# User.net
KiCad netlist of a schematic drawn in Altium Designer
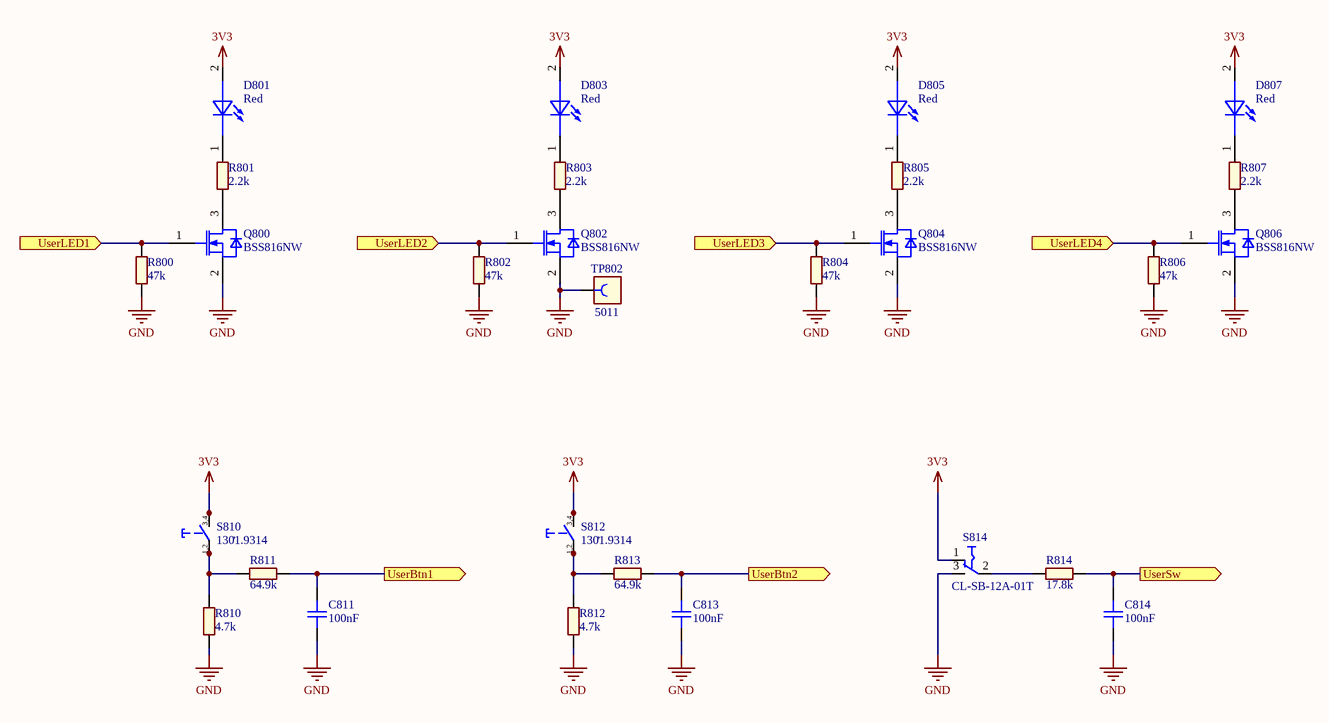
[diagram p0: User.SchDoc]

(export (version "E")
  (design (tool "Eeschema 10.0.6"))
  (components
    (comp (ref "C811")
      (value "100nF")
      (footprint "CAPC1608X90N-2")
      (description "CAP / CERA / 100nF / 50V / 10% / X7R (EIA) / -55°C to 125°C / 0603 / SMD / -")
      (fields (field (name "MANUFACTURER") "AVX"))
      (libsource (lib "PCBLibraryData") (part "CAP-SGL-STD-02P_00000001"))
    )
    (comp (ref "C813")
      (value "100nF")
      (footprint "CAPC1608X90N-2")
      (description "CAP / CERA / 100nF / 50V / 10% / X7R (EIA) / -55°C to 125°C / 0603 / SMD / -")
      (fields (field (name "MANUFACTURER") "AVX"))
      (libsource (lib "PCBLibraryData") (part "CAP-SGL-STD-02P_00000001"))
    )
    (comp (ref "C814")
      (value "100nF")
      (footprint "CAPC1608X90N-2")
      (description "CAP / CERA / 100nF / 50V / 10% / X7R (EIA) / -55°C to 125°C / 0603 / SMD / -")
      (fields (field (name "MANUFACTURER") "AVX"))
      (libsource (lib "PCBLibraryData") (part "CAP-SGL-STD-02P_00000001"))
    )
    (comp (ref "D801")
      (value "Red")
      (footprint "LEDSC160X80X80-2N-1")
      (description "WL-SMCW SMT Mono-color Chip LED Waterclear, Red,630nm")
      (fields (field (name "MANUFACTURER") "Wurth Elektronik"))
      (libsource (lib "PCBLibraryData") (part "d_led_a"))
    )
    (comp (ref "D803")
      (value "Red")
      (footprint "LEDSC160X80X80-2N-1")
      (description "WL-SMCW SMT Mono-color Chip LED Waterclear, Red,630nm")
      (fields (field (name "MANUFACTURER") "Wurth Elektronik"))
      (libsource (lib "PCBLibraryData") (part "d_led_a"))
    )
    (comp (ref "D805")
      (value "Red")
      (footprint "LEDSC160X80X80-2N-1")
      (description "WL-SMCW SMT Mono-color Chip LED Waterclear, Red,630nm")
      (fields (field (name "MANUFACTURER") "Wurth Elektronik"))
      (libsource (lib "PCBLibraryData") (part "d_led_a"))
    )
    (comp (ref "D807")
      (value "Red")
      (footprint "LEDSC160X80X80-2N-1")
      (description "WL-SMCW SMT Mono-color Chip LED Waterclear, Red,630nm")
      (fields (field (name "MANUFACTURER") "Wurth Elektronik"))
      (libsource (lib "PCBLibraryData") (part "d_led_a"))
    )
    (comp (ref "Q800")
      (value "BSS816NW")
      (footprint "SOT65P210X100-3N-1-V")
      (description "OptiMOS 2 Small-Signal-Transistor")
      (fields (field (name "MANUFACTURER") "Infineon Technologies"))
      (libsource (lib "PCBLibraryData") (part "igfet_n_ch_dep_dio_1g2s3d_3p"))
    )
    (comp (ref "Q802")
      (value "BSS816NW")
      (footprint "SOT65P210X100-3N-1-V")
      (description "OptiMOS 2 Small-Signal-Transistor")
      (fields (field (name "MANUFACTURER") "Infineon Technologies"))
      (libsource (lib "PCBLibraryData") (part "igfet_n_ch_dep_dio_1g2s3d_3p"))
    )
    (comp (ref "Q804")
      (value "BSS816NW")
      (footprint "SOT65P210X100-3N-1-V")
      (description "OptiMOS 2 Small-Signal-Transistor")
      (fields (field (name "MANUFACTURER") "Infineon Technologies"))
      (libsource (lib "PCBLibraryData") (part "igfet_n_ch_dep_dio_1g2s3d_3p"))
    )
    (comp (ref "Q806")
      (value "BSS816NW")
      (footprint "SOT65P210X100-3N-1-V")
      (description "OptiMOS 2 Small-Signal-Transistor")
      (fields (field (name "MANUFACTURER") "Infineon Technologies"))
      (libsource (lib "PCBLibraryData") (part "igfet_n_ch_dep_dio_1g2s3d_3p"))
    )
    (comp (ref "R800")
      (value "47k")
      (footprint "RESC1609X50N")
      (description "RES / STD / 47k / 100mW / 1% / 100ppm/K / -55°C to 155°C / 0603 / SMD / -")
      (fields (field (name "LEGACY PARTNUMBER") "RES01801333") (field (name "MANUFACTURER") "Vishay"))
      (libsource (lib "PCBLibraryData") (part "RES-SGL-STD-02P_00000006"))
    )
    (comp (ref "R801")
      (value "2.2k")
      (footprint "RESC1609X50N")
      (description "RES / STD / 2.2k / 100mW / 1% / 100ppm/K / -55°C to 155°C / 0603 / SMD / -")
      (fields (field (name "LEGACY PARTNUMBER") "RES01801179") (field (name "MANUFACTURER") "Vishay"))
      (libsource (lib "") (part "RES-SGL-STD-02P_00000006_1"))
    )
    (comp (ref "R802")
      (value "47k")
      (footprint "RESC1609X50N")
      (description "RES / STD / 47k / 100mW / 1% / 100ppm/K / -55°C to 155°C / 0603 / SMD / -")
      (fields (field (name "LEGACY PARTNUMBER") "RES01801333") (field (name "MANUFACTURER") "Vishay"))
      (libsource (lib "PCBLibraryData") (part "RES-SGL-STD-02P_00000006"))
    )
    (comp (ref "R803")
      (value "2.2k")
      (footprint "RESC1609X50N")
      (description "RES / STD / 2.2k / 100mW / 1% / 100ppm/K / -55°C to 155°C / 0603 / SMD / -")
      (fields (field (name "LEGACY PARTNUMBER") "RES01801179") (field (name "MANUFACTURER") "Vishay"))
      (libsource (lib "") (part "RES-SGL-STD-02P_00000006_1"))
    )
    (comp (ref "R804")
      (value "47k")
      (footprint "RESC1609X50N")
      (description "RES / STD / 47k / 100mW / 1% / 100ppm/K / -55°C to 155°C / 0603 / SMD / -")
      (fields (field (name "LEGACY PARTNUMBER") "RES01801333") (field (name "MANUFACTURER") "Vishay"))
      (libsource (lib "PCBLibraryData") (part "RES-SGL-STD-02P_00000006"))
    )
    (comp (ref "R805")
      (value "2.2k")
      (footprint "RESC1609X50N")
      (description "RES / STD / 2.2k / 100mW / 1% / 100ppm/K / -55°C to 155°C / 0603 / SMD / -")
      (fields (field (name "LEGACY PARTNUMBER") "RES01801179") (field (name "MANUFACTURER") "Vishay"))
      (libsource (lib "") (part "RES-SGL-STD-02P_00000006_1"))
    )
    (comp (ref "R806")
      (value "47k")
      (footprint "RESC1609X50N")
      (description "RES / STD / 47k / 100mW / 1% / 100ppm/K / -55°C to 155°C / 0603 / SMD / -")
      (fields (field (name "LEGACY PARTNUMBER") "RES01801333") (field (name "MANUFACTURER") "Vishay"))
      (libsource (lib "PCBLibraryData") (part "RES-SGL-STD-02P_00000006"))
    )
    (comp (ref "R807")
      (value "2.2k")
      (footprint "RESC1609X50N")
      (description "RES / STD / 2.2k / 100mW / 1% / 100ppm/K / -55°C to 155°C / 0603 / SMD / -")
      (fields (field (name "LEGACY PARTNUMBER") "RES01801179") (field (name "MANUFACTURER") "Vishay"))
      (libsource (lib "") (part "RES-SGL-STD-02P_00000006_1"))
    )
    (comp (ref "R810")
      (value "4.7k")
      (footprint "RESC1609X50N")
      (description "RES / STD / 4.7k / 100mW / 1% / 100ppm/K / -55°C to 155°C / 0603 / SMD / -")
      (fields (field (name "LEGACY PARTNUMBER") "RES01801219") (field (name "MANUFACTURER") "Vishay"))
      (libsource (lib "PCBLibraryData") (part "RES-SGL-STD-02P_00000006"))
    )
    (comp (ref "R811")
      (value "64.9k")
      (footprint "RESC1609X50N")
      (description "RES / STD / 64.9k / 100mW / 1% / 100ppm/K / -55°C to 155°C / 0603 / SMD / -")
      (fields (field (name "LEGACY PARTNUMBER") "RES01801350") (field (name "MANUFACTURER") "Vishay"))
      (libsource (lib "") (part "RES-SGL-STD-02P_00000006_2"))
    )
    (comp (ref "R812")
      (value "4.7k")
      (footprint "RESC1609X50N")
      (description "RES / STD / 4.7k / 100mW / 1% / 100ppm/K / -55°C to 155°C / 0603 / SMD / -")
      (fields (field (name "LEGACY PARTNUMBER") "RES01801219") (field (name "MANUFACTURER") "Vishay"))
      (libsource (lib "PCBLibraryData") (part "RES-SGL-STD-02P_00000006"))
    )
    (comp (ref "R813")
      (value "64.9k")
      (footprint "RESC1609X50N")
      (description "RES / STD / 64.9k / 100mW / 1% / 100ppm/K / -55°C to 155°C / 0603 / SMD / -")
      (fields (field (name "LEGACY PARTNUMBER") "RES01801350") (field (name "MANUFACTURER") "Vishay"))
      (libsource (lib "") (part "RES-SGL-STD-02P_00000006_2"))
    )
    (comp (ref "R814")
      (value "17.8k")
      (footprint "RESC1609X50N")
      (description "RES / STD / 17.8k / 100mW / 1% / 100ppm/K / -55°C to 155°C / 0603 / SMD / -")
      (fields (field (name "LEGACY PARTNUMBER") "RES01801283") (field (name "MANUFACTURER") "Vishay"))
      (libsource (lib "") (part "RES-SGL-STD-02P_00000006_2"))
    )
    (comp (ref "S810")
      (value "1301.9314")
      (footprint "SW-SMD-1301.9314")
      (description "Pushbutton Tactile Switch, Single Pole Single Throw, 4 Pins")
      (fields (field (name "LEGACY PARTNUMBER") "CON01500305") (field (name "MANUFACTURER") "Schurter"))
      (libsource (lib "PCBLibraryData") (part "sw_sr_no12_34_4p"))
    )
    (comp (ref "S812")
      (value "1301.9314")
      (footprint "SW-SMD-1301.9314")
      (description "Pushbutton Tactile Switch, Single Pole Single Throw, 4 Pins")
      (fields (field (name "LEGACY PARTNUMBER") "CON01500305") (field (name "MANUFACTURER") "Schurter"))
      (libsource (lib "PCBLibraryData") (part "sw_sr_no12_34_4p"))
    )
    (comp (ref "S814")
      (value "CL-SB-12A-01T")
      (footprint "SW-SMD-CL-SB-12A-01T")
      (description "Slid Switch, 12V, 200mA")
      (fields (field (name "MANUFACTURER") "NIDEC COPAL ELECTRONICS, Inc."))
      (libsource (lib "PCBLibraryData") (part "sw_co213_3p"))
    )
    (comp (ref "TP802")
      (value "5011")
      (footprint "CON-THT-TP-5011")
      (description "PC Test Point-Multipurpose THT, Black")
      (fields
        (field (name "LEGACY PARTNUMBER") "CON01500530")
        (field (name "MANUFACTURER") "Keystone Electronics Corp.")
      )
      (libsource (lib "PCBLibraryData") (part "connector_1_f"))
    )
  )
  (nets
    (net (code "1") (name "/UserBtn1") (class "Default")
      (node (ref "C811") (pin "2") (pinfunction "2_2") (pintype "passive"))
      (node (ref "R811") (pin "1") (pinfunction "1_1") (pintype "passive"))
    )
    (net (code "2") (name "/UserBtn2") (class "Default")
      (node (ref "C813") (pin "2") (pinfunction "2_2") (pintype "passive"))
      (node (ref "R813") (pin "1") (pinfunction "1_1") (pintype "passive"))
    )
    (net (code "3") (name "/UserLED1") (class "Default")
      (node (ref "Q800") (pin "1") (pinfunction "GATE_1") (pintype "passive"))
      (node (ref "R800") (pin "2") (pinfunction "2_2") (pintype "passive"))
    )
    (net (code "4") (name "/UserLED2") (class "Default")
      (node (ref "Q802") (pin "1") (pinfunction "GATE_1") (pintype "passive"))
      (node (ref "R802") (pin "2") (pinfunction "2_2") (pintype "passive"))
    )
    (net (code "5") (name "/UserLED3") (class "Default")
      (node (ref "Q804") (pin "1") (pinfunction "GATE_1") (pintype "passive"))
      (node (ref "R804") (pin "2") (pinfunction "2_2") (pintype "passive"))
    )
    (net (code "6") (name "/UserLED4") (class "Default")
      (node (ref "Q806") (pin "1") (pinfunction "GATE_1") (pintype "passive"))
      (node (ref "R806") (pin "2") (pinfunction "2_2") (pintype "passive"))
    )
    (net (code "7") (name "/UserSw") (class "Default")
      (node (ref "C814") (pin "2") (pinfunction "2_2") (pintype "passive"))
      (node (ref "R814") (pin "1") (pinfunction "1_1") (pintype "passive"))
    )
    (net (code "8") (name "3V3") (class "Default")
      (node (ref "D801") (pin "2") (pinfunction "Anode_2") (pintype "passive"))
      (node (ref "D803") (pin "2") (pinfunction "Anode_2") (pintype "passive"))
      (node (ref "D805") (pin "2") (pinfunction "Anode_2") (pintype "passive"))
      (node (ref "D807") (pin "2") (pinfunction "Anode_2") (pintype "passive"))
      (node (ref "S810") (pin "3") (pinfunction "3_3") (pintype "passive"))
      (node (ref "S810") (pin "4") (pinfunction "4_4") (pintype "passive"))
      (node (ref "S812") (pin "3") (pinfunction "3_3") (pintype "passive"))
      (node (ref "S812") (pin "4") (pinfunction "4_4") (pintype "passive"))
      (node (ref "S814") (pin "1") (pinfunction "1_1") (pintype "passive"))
    )
    (net (code "9") (name "GND") (class "Default")
      (node (ref "C811") (pin "1") (pinfunction "1_1") (pintype "passive"))
      (node (ref "C813") (pin "1") (pinfunction "1_1") (pintype "passive"))
      (node (ref "C814") (pin "1") (pinfunction "1_1") (pintype "passive"))
      (node (ref "Q800") (pin "2") (pinfunction "SOURCE_2") (pintype "passive"))
      (node (ref "Q802") (pin "2") (pinfunction "SOURCE_2") (pintype "passive"))
      (node (ref "Q804") (pin "2") (pinfunction "SOURCE_2") (pintype "passive"))
      (node (ref "Q806") (pin "2") (pinfunction "SOURCE_2") (pintype "passive"))
      (node (ref "R800") (pin "1") (pinfunction "1_1") (pintype "passive"))
      (node (ref "R802") (pin "1") (pinfunction "1_1") (pintype "passive"))
      (node (ref "R804") (pin "1") (pinfunction "1_1") (pintype "passive"))
      (node (ref "R806") (pin "1") (pinfunction "1_1") (pintype "passive"))
      (node (ref "R810") (pin "1") (pinfunction "1_1") (pintype "passive"))
      (node (ref "R812") (pin "1") (pinfunction "1_1") (pintype "passive"))
      (node (ref "S814") (pin "3") (pinfunction "3_3") (pintype "passive"))
      (node (ref "TP802") (pin "1") (pinfunction "1_1") (pintype "passive"))
    )
    (net (code "10") (name "Net-(D801-Cathode)") (class "Default")
      (node (ref "D801") (pin "1") (pinfunction "Cathode_1") (pintype "passive"))
      (node (ref "R801") (pin "1") (pinfunction "1_1") (pintype "passive"))
    )
    (net (code "11") (name "Net-(D803-Cathode)") (class "Default")
      (node (ref "D803") (pin "1") (pinfunction "Cathode_1") (pintype "passive"))
      (node (ref "R803") (pin "1") (pinfunction "1_1") (pintype "passive"))
    )
    (net (code "12") (name "Net-(D805-Cathode)") (class "Default")
      (node (ref "D805") (pin "1") (pinfunction "Cathode_1") (pintype "passive"))
      (node (ref "R805") (pin "1") (pinfunction "1_1") (pintype "passive"))
    )
    (net (code "13") (name "Net-(D807-Cathode)") (class "Default")
      (node (ref "D807") (pin "1") (pinfunction "Cathode_1") (pintype "passive"))
      (node (ref "R807") (pin "1") (pinfunction "1_1") (pintype "passive"))
    )
    (net (code "14") (name "Net-(Q800-DRAIN)") (class "Default")
      (node (ref "Q800") (pin "3") (pinfunction "DRAIN_3") (pintype "passive"))
      (node (ref "R801") (pin "2") (pinfunction "2_2") (pintype "passive"))
    )
    (net (code "15") (name "Net-(Q802-DRAIN)") (class "Default")
      (node (ref "Q802") (pin "3") (pinfunction "DRAIN_3") (pintype "passive"))
      (node (ref "R803") (pin "2") (pinfunction "2_2") (pintype "passive"))
    )
    (net (code "16") (name "Net-(Q804-DRAIN)") (class "Default")
      (node (ref "Q804") (pin "3") (pinfunction "DRAIN_3") (pintype "passive"))
      (node (ref "R805") (pin "2") (pinfunction "2_2") (pintype "passive"))
    )
    (net (code "17") (name "Net-(Q806-DRAIN)") (class "Default")
      (node (ref "Q806") (pin "3") (pinfunction "DRAIN_3") (pintype "passive"))
      (node (ref "R807") (pin "2") (pinfunction "2_2") (pintype "passive"))
    )
    (net (code "18") (name "Net-(R810-Pad2)") (class "Default")
      (node (ref "R810") (pin "2") (pinfunction "2_2") (pintype "passive"))
      (node (ref "R811") (pin "2") (pinfunction "2_2") (pintype "passive"))
      (node (ref "S810") (pin "1") (pinfunction "1_1") (pintype "passive"))
      (node (ref "S810") (pin "2") (pinfunction "2_2") (pintype "passive"))
    )
    (net (code "19") (name "Net-(R812-Pad2)") (class "Default")
      (node (ref "R812") (pin "2") (pinfunction "2_2") (pintype "passive"))
      (node (ref "R813") (pin "2") (pinfunction "2_2") (pintype "passive"))
      (node (ref "S812") (pin "1") (pinfunction "1_1") (pintype "passive"))
      (node (ref "S812") (pin "2") (pinfunction "2_2") (pintype "passive"))
    )
    (net (code "20") (name "Net-(R814-Pad2)") (class "Default")
      (node (ref "R814") (pin "2") (pinfunction "2_2") (pintype "passive"))
      (node (ref "S814") (pin "2") (pinfunction "2_2") (pintype "passive"))
    )
  )
)
